# IO_Power_Decoupling.net
KiCad netlist of a schematic drawn in Altium Designer
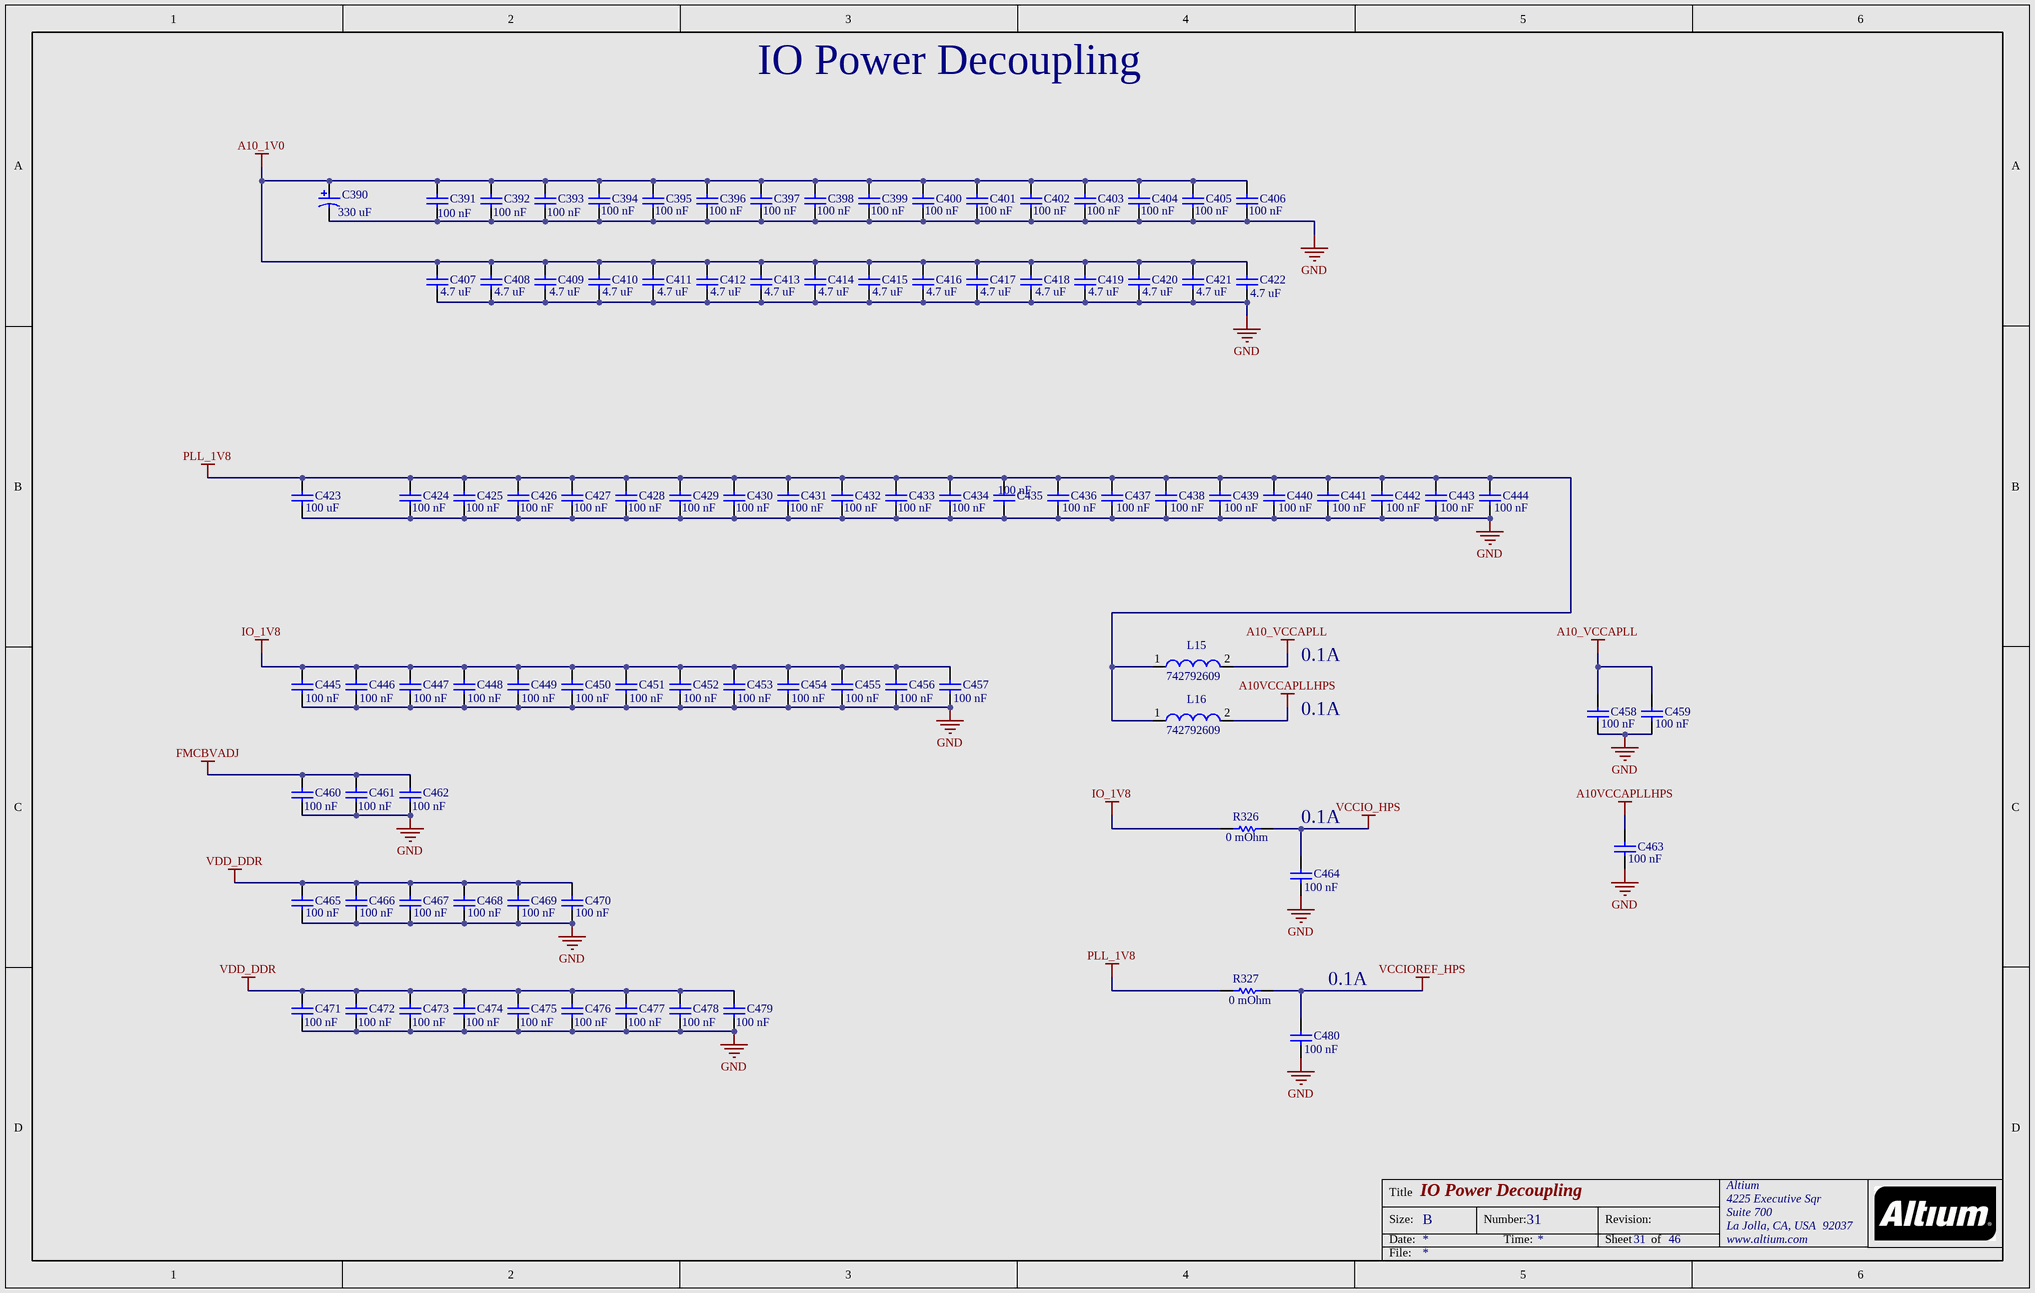
[diagram p0: IO_Power_Decoupling.SchDoc]

(export (version "E")
  (design (tool "Eeschema 10.0.6"))
  (components
    (comp (ref "C390")
      (value "T520B337M2R5ATE045")
      (footprint "KEMT-520-B-2_M")
      (description "Tantalum Capacitor, 330 uF, +/- 20%, 2.5 V, -55 to 105 degC, 2-Pin Molded, RoHS, Tape and Reel")
      (fields (field (name "CAPACITANCE") "330 uF"))
      (libsource (lib "Altium Content Vault") (part "CMP-1664-00002-2"))
    )
    (comp (ref "C391")
      (value "GRM033R60J104KE19D")
      (footprint "CAPC0603X33X15LL03T05")
      (description "Chip Capacitor, 100 nF, +/- 10%, 6.3 V, -55 to 85 degC, 0201 (0603 Metric), RoHS, Tape and Reel")
      (fields
        (field (name "TOLERANCE") "10%")
        (field (name "CAPACITANCE") "100 nF")
        (field (name "MANUFACTURER") "Basic Passives")
      )
      (libsource (lib "Altium Content Vault") (part "CAP-NP-2"))
    )
    (comp (ref "C392")
      (value "GRM033R60J104KE19D")
      (footprint "CAPC0603X33X15LL03T05")
      (description "Chip Capacitor, 100 nF, +/- 10%, 6.3 V, -55 to 85 degC, 0201 (0603 Metric), RoHS, Tape and Reel")
      (fields
        (field (name "TOLERANCE") "10%")
        (field (name "CAPACITANCE") "100 nF")
        (field (name "MANUFACTURER") "Basic Passives")
      )
      (libsource (lib "Altium Content Vault") (part "CAP-NP-2"))
    )
    (comp (ref "C393")
      (value "GRM033R60J104KE19D")
      (footprint "CAPC0603X33X15LL03T05")
      (description "Chip Capacitor, 100 nF, +/- 10%, 6.3 V, -55 to 85 degC, 0201 (0603 Metric), RoHS, Tape and Reel")
      (fields
        (field (name "TOLERANCE") "10%")
        (field (name "CAPACITANCE") "100 nF")
        (field (name "MANUFACTURER") "Basic Passives")
      )
      (libsource (lib "Altium Content Vault") (part "CAP-NP-2"))
    )
    (comp (ref "C394")
      (value "GRM033R60J104KE19D")
      (footprint "CAPC0603X33X15LL03T05")
      (description "Chip Capacitor, 100 nF, +/- 10%, 6.3 V, -55 to 85 degC, 0201 (0603 Metric), RoHS, Tape and Reel")
      (fields
        (field (name "TOLERANCE") "10%")
        (field (name "CAPACITANCE") "100 nF")
        (field (name "MANUFACTURER") "Basic Passives")
      )
      (libsource (lib "Altium Content Vault") (part "CAP-NP-2"))
    )
    (comp (ref "C395")
      (value "GRM033R60J104KE19D")
      (footprint "CAPC0603X33X15LL03T05")
      (description "Chip Capacitor, 100 nF, +/- 10%, 6.3 V, -55 to 85 degC, 0201 (0603 Metric), RoHS, Tape and Reel")
      (fields
        (field (name "TOLERANCE") "10%")
        (field (name "CAPACITANCE") "100 nF")
        (field (name "MANUFACTURER") "Basic Passives")
      )
      (libsource (lib "Altium Content Vault") (part "CAP-NP-2"))
    )
    (comp (ref "C396")
      (value "GRM033R60J104KE19D")
      (footprint "CAPC0603X33X15LL03T05")
      (description "Chip Capacitor, 100 nF, +/- 10%, 6.3 V, -55 to 85 degC, 0201 (0603 Metric), RoHS, Tape and Reel")
      (fields
        (field (name "TOLERANCE") "10%")
        (field (name "CAPACITANCE") "100 nF")
        (field (name "MANUFACTURER") "Basic Passives")
      )
      (libsource (lib "Altium Content Vault") (part "CAP-NP-2"))
    )
    (comp (ref "C397")
      (value "GRM033R60J104KE19D")
      (footprint "CAPC0603X33X15LL03T05")
      (description "Chip Capacitor, 100 nF, +/- 10%, 6.3 V, -55 to 85 degC, 0201 (0603 Metric), RoHS, Tape and Reel")
      (fields
        (field (name "TOLERANCE") "10%")
        (field (name "CAPACITANCE") "100 nF")
        (field (name "MANUFACTURER") "Basic Passives")
      )
      (libsource (lib "Altium Content Vault") (part "CAP-NP-2"))
    )
    (comp (ref "C398")
      (value "GRM033R60J104KE19D")
      (footprint "CAPC0603X33X15LL03T05")
      (description "Chip Capacitor, 100 nF, +/- 10%, 6.3 V, -55 to 85 degC, 0201 (0603 Metric), RoHS, Tape and Reel")
      (fields
        (field (name "TOLERANCE") "10%")
        (field (name "CAPACITANCE") "100 nF")
        (field (name "MANUFACTURER") "Basic Passives")
      )
      (libsource (lib "Altium Content Vault") (part "CAP-NP-2"))
    )
    (comp (ref "C399")
      (value "GRM033R60J104KE19D")
      (footprint "CAPC0603X33X15LL03T05")
      (description "Chip Capacitor, 100 nF, +/- 10%, 6.3 V, -55 to 85 degC, 0201 (0603 Metric), RoHS, Tape and Reel")
      (fields
        (field (name "TOLERANCE") "10%")
        (field (name "CAPACITANCE") "100 nF")
        (field (name "MANUFACTURER") "Basic Passives")
      )
      (libsource (lib "Altium Content Vault") (part "CAP-NP-2"))
    )
    (comp (ref "C400")
      (value "GRM033R60J104KE19D")
      (footprint "CAPC0603X33X15LL03T05")
      (description "Chip Capacitor, 100 nF, +/- 10%, 6.3 V, -55 to 85 degC, 0201 (0603 Metric), RoHS, Tape and Reel")
      (fields
        (field (name "TOLERANCE") "10%")
        (field (name "CAPACITANCE") "100 nF")
        (field (name "MANUFACTURER") "Basic Passives")
      )
      (libsource (lib "Altium Content Vault") (part "CAP-NP-2"))
    )
    (comp (ref "C401")
      (value "GRM033R60J104KE19D")
      (footprint "CAPC0603X33X15LL03T05")
      (description "Chip Capacitor, 100 nF, +/- 10%, 6.3 V, -55 to 85 degC, 0201 (0603 Metric), RoHS, Tape and Reel")
      (fields
        (field (name "TOLERANCE") "10%")
        (field (name "CAPACITANCE") "100 nF")
        (field (name "MANUFACTURER") "Basic Passives")
      )
      (libsource (lib "Altium Content Vault") (part "CAP-NP-2"))
    )
    (comp (ref "C402")
      (value "GRM033R60J104KE19D")
      (footprint "CAPC0603X33X15LL03T05")
      (description "Chip Capacitor, 100 nF, +/- 10%, 6.3 V, -55 to 85 degC, 0201 (0603 Metric), RoHS, Tape and Reel")
      (fields
        (field (name "TOLERANCE") "10%")
        (field (name "CAPACITANCE") "100 nF")
        (field (name "MANUFACTURER") "Basic Passives")
      )
      (libsource (lib "Altium Content Vault") (part "CAP-NP-2"))
    )
    (comp (ref "C403")
      (value "GRM033R60J104KE19D")
      (footprint "CAPC0603X33X15LL03T05")
      (description "Chip Capacitor, 100 nF, +/- 10%, 6.3 V, -55 to 85 degC, 0201 (0603 Metric), RoHS, Tape and Reel")
      (fields
        (field (name "TOLERANCE") "10%")
        (field (name "CAPACITANCE") "100 nF")
        (field (name "MANUFACTURER") "Basic Passives")
      )
      (libsource (lib "Altium Content Vault") (part "CAP-NP-2"))
    )
    (comp (ref "C404")
      (value "GRM033R60J104KE19D")
      (footprint "CAPC0603X33X15LL03T05")
      (description "Chip Capacitor, 100 nF, +/- 10%, 6.3 V, -55 to 85 degC, 0201 (0603 Metric), RoHS, Tape and Reel")
      (fields
        (field (name "TOLERANCE") "10%")
        (field (name "CAPACITANCE") "100 nF")
        (field (name "MANUFACTURER") "Basic Passives")
      )
      (libsource (lib "Altium Content Vault") (part "CAP-NP-2"))
    )
    (comp (ref "C405")
      (value "GRM033R60J104KE19D")
      (footprint "CAPC0603X33X15LL03T05")
      (description "Chip Capacitor, 100 nF, +/- 10%, 6.3 V, -55 to 85 degC, 0201 (0603 Metric), RoHS, Tape and Reel")
      (fields
        (field (name "TOLERANCE") "10%")
        (field (name "CAPACITANCE") "100 nF")
        (field (name "MANUFACTURER") "Basic Passives")
      )
      (libsource (lib "Altium Content Vault") (part "CAP-NP-2"))
    )
    (comp (ref "C406")
      (value "GRM033R60J104KE19D")
      (footprint "CAPC0603X33X15LL03T05")
      (description "Chip Capacitor, 100 nF, +/- 10%, 6.3 V, -55 to 85 degC, 0201 (0603 Metric), RoHS, Tape and Reel")
      (fields
        (field (name "TOLERANCE") "10%")
        (field (name "CAPACITANCE") "100 nF")
        (field (name "MANUFACTURER") "Basic Passives")
      )
      (libsource (lib "Altium Content Vault") (part "CAP-NP-2"))
    )
    (comp (ref "C407")
      (value "GRM155R60J475ME87D")
      (footprint "CAPC1005X55X25LL05T10")
      (description "Chip Capacitor, 4.7 uF, +/- 20%, 6.3 V, -55 to 85 degC, 0402 (1005 Metric), RoHS, Tape and Reel")
      (fields
        (field (name "TOLERANCE") "20%")
        (field (name "CAPACITANCE") "4.7 uF")
        (field (name "MANUFACTURER") "Basic Passives")
      )
      (libsource (lib "Altium Content Vault") (part "CAP-NP-2"))
    )
    (comp (ref "C408")
      (value "GRM155R60J475ME87D")
      (footprint "CAPC1005X55X25LL05T10")
      (description "Chip Capacitor, 4.7 uF, +/- 20%, 6.3 V, -55 to 85 degC, 0402 (1005 Metric), RoHS, Tape and Reel")
      (fields
        (field (name "TOLERANCE") "20%")
        (field (name "CAPACITANCE") "4.7 uF")
        (field (name "MANUFACTURER") "Basic Passives")
      )
      (libsource (lib "Altium Content Vault") (part "CAP-NP-2"))
    )
    (comp (ref "C409")
      (value "GRM155R60J475ME87D")
      (footprint "CAPC1005X55X25LL05T10")
      (description "Chip Capacitor, 4.7 uF, +/- 20%, 6.3 V, -55 to 85 degC, 0402 (1005 Metric), RoHS, Tape and Reel")
      (fields
        (field (name "TOLERANCE") "20%")
        (field (name "CAPACITANCE") "4.7 uF")
        (field (name "MANUFACTURER") "Basic Passives")
      )
      (libsource (lib "Altium Content Vault") (part "CAP-NP-2"))
    )
    (comp (ref "C410")
      (value "GRM155R60J475ME87D")
      (footprint "CAPC1005X55X25LL05T10")
      (description "Chip Capacitor, 4.7 uF, +/- 20%, 6.3 V, -55 to 85 degC, 0402 (1005 Metric), RoHS, Tape and Reel")
      (fields
        (field (name "TOLERANCE") "20%")
        (field (name "CAPACITANCE") "4.7 uF")
        (field (name "MANUFACTURER") "Basic Passives")
      )
      (libsource (lib "Altium Content Vault") (part "CAP-NP-2"))
    )
    (comp (ref "C411")
      (value "GRM155R60J475ME87D")
      (footprint "CAPC1005X55X25LL05T10")
      (description "Chip Capacitor, 4.7 uF, +/- 20%, 6.3 V, -55 to 85 degC, 0402 (1005 Metric), RoHS, Tape and Reel")
      (fields
        (field (name "TOLERANCE") "20%")
        (field (name "CAPACITANCE") "4.7 uF")
        (field (name "MANUFACTURER") "Basic Passives")
      )
      (libsource (lib "Altium Content Vault") (part "CAP-NP-2"))
    )
    (comp (ref "C412")
      (value "GRM155R60J475ME87D")
      (footprint "CAPC1005X55X25LL05T10")
      (description "Chip Capacitor, 4.7 uF, +/- 20%, 6.3 V, -55 to 85 degC, 0402 (1005 Metric), RoHS, Tape and Reel")
      (fields
        (field (name "TOLERANCE") "20%")
        (field (name "CAPACITANCE") "4.7 uF")
        (field (name "MANUFACTURER") "Basic Passives")
      )
      (libsource (lib "Altium Content Vault") (part "CAP-NP-2"))
    )
    (comp (ref "C413")
      (value "GRM155R60J475ME87D")
      (footprint "CAPC1005X55X25LL05T10")
      (description "Chip Capacitor, 4.7 uF, +/- 20%, 6.3 V, -55 to 85 degC, 0402 (1005 Metric), RoHS, Tape and Reel")
      (fields
        (field (name "TOLERANCE") "20%")
        (field (name "CAPACITANCE") "4.7 uF")
        (field (name "MANUFACTURER") "Basic Passives")
      )
      (libsource (lib "Altium Content Vault") (part "CAP-NP-2"))
    )
    (comp (ref "C414")
      (value "GRM155R60J475ME87D")
      (footprint "CAPC1005X55X25LL05T10")
      (description "Chip Capacitor, 4.7 uF, +/- 20%, 6.3 V, -55 to 85 degC, 0402 (1005 Metric), RoHS, Tape and Reel")
      (fields
        (field (name "TOLERANCE") "20%")
        (field (name "CAPACITANCE") "4.7 uF")
        (field (name "MANUFACTURER") "Basic Passives")
      )
      (libsource (lib "Altium Content Vault") (part "CAP-NP-2"))
    )
    (comp (ref "C415")
      (value "GRM155R60J475ME87D")
      (footprint "CAPC1005X55X25LL05T10")
      (description "Chip Capacitor, 4.7 uF, +/- 20%, 6.3 V, -55 to 85 degC, 0402 (1005 Metric), RoHS, Tape and Reel")
      (fields
        (field (name "TOLERANCE") "20%")
        (field (name "CAPACITANCE") "4.7 uF")
        (field (name "MANUFACTURER") "Basic Passives")
      )
      (libsource (lib "Altium Content Vault") (part "CAP-NP-2"))
    )
    (comp (ref "C416")
      (value "GRM155R60J475ME87D")
      (footprint "CAPC1005X55X25LL05T10")
      (description "Chip Capacitor, 4.7 uF, +/- 20%, 6.3 V, -55 to 85 degC, 0402 (1005 Metric), RoHS, Tape and Reel")
      (fields
        (field (name "TOLERANCE") "20%")
        (field (name "CAPACITANCE") "4.7 uF")
        (field (name "MANUFACTURER") "Basic Passives")
      )
      (libsource (lib "Altium Content Vault") (part "CAP-NP-2"))
    )
    (comp (ref "C417")
      (value "GRM155R60J475ME87D")
      (footprint "CAPC1005X55X25LL05T10")
      (description "Chip Capacitor, 4.7 uF, +/- 20%, 6.3 V, -55 to 85 degC, 0402 (1005 Metric), RoHS, Tape and Reel")
      (fields
        (field (name "TOLERANCE") "20%")
        (field (name "CAPACITANCE") "4.7 uF")
        (field (name "MANUFACTURER") "Basic Passives")
      )
      (libsource (lib "Altium Content Vault") (part "CAP-NP-2"))
    )
    (comp (ref "C418")
      (value "GRM155R60J475ME87D")
      (footprint "CAPC1005X55X25LL05T10")
      (description "Chip Capacitor, 4.7 uF, +/- 20%, 6.3 V, -55 to 85 degC, 0402 (1005 Metric), RoHS, Tape and Reel")
      (fields
        (field (name "TOLERANCE") "20%")
        (field (name "CAPACITANCE") "4.7 uF")
        (field (name "MANUFACTURER") "Basic Passives")
      )
      (libsource (lib "Altium Content Vault") (part "CAP-NP-2"))
    )
    (comp (ref "C419")
      (value "GRM155R60J475ME87D")
      (footprint "CAPC1005X55X25LL05T10")
      (description "Chip Capacitor, 4.7 uF, +/- 20%, 6.3 V, -55 to 85 degC, 0402 (1005 Metric), RoHS, Tape and Reel")
      (fields
        (field (name "TOLERANCE") "20%")
        (field (name "CAPACITANCE") "4.7 uF")
        (field (name "MANUFACTURER") "Basic Passives")
      )
      (libsource (lib "Altium Content Vault") (part "CAP-NP-2"))
    )
    (comp (ref "C420")
      (value "GRM155R60J475ME87D")
      (footprint "CAPC1005X55X25LL05T10")
      (description "Chip Capacitor, 4.7 uF, +/- 20%, 6.3 V, -55 to 85 degC, 0402 (1005 Metric), RoHS, Tape and Reel")
      (fields
        (field (name "TOLERANCE") "20%")
        (field (name "CAPACITANCE") "4.7 uF")
        (field (name "MANUFACTURER") "Basic Passives")
      )
      (libsource (lib "Altium Content Vault") (part "CAP-NP-2"))
    )
    (comp (ref "C421")
      (value "GRM155R60J475ME87D")
      (footprint "CAPC1005X55X25LL05T10")
      (description "Chip Capacitor, 4.7 uF, +/- 20%, 6.3 V, -55 to 85 degC, 0402 (1005 Metric), RoHS, Tape and Reel")
      (fields
        (field (name "TOLERANCE") "20%")
        (field (name "CAPACITANCE") "4.7 uF")
        (field (name "MANUFACTURER") "Basic Passives")
      )
      (libsource (lib "Altium Content Vault") (part "CAP-NP-2"))
    )
    (comp (ref "C422")
      (value "GRM155R60J475ME87D")
      (footprint "CAPC1005X55X25LL05T10")
      (description "Chip Capacitor, 4.7 uF, +/- 20%, 6.3 V, -55 to 85 degC, 0402 (1005 Metric), RoHS, Tape and Reel")
      (fields
        (field (name "TOLERANCE") "20%")
        (field (name "CAPACITANCE") "4.7 uF")
        (field (name "MANUFACTURER") "Basic Passives")
      )
      (libsource (lib "Altium Content Vault") (part "CAP-NP-2"))
    )
    (comp (ref "C423")
      (value "GRM31CR60J107ME39L")
      (footprint "CAPC3216X190X55ML30T25")
      (description "Chip Capacitor, 100 uF, +/- 20%, 6.3 V, -55 to 85 degC, 1206 (3216 Metric), RoHS, Tape and Reel")
      (fields (field (name "TOLERANCE") "20%") (field (name "CAPACITANCE") "100 uF"))
      (libsource (lib "Altium Content Vault") (part "CAP-NP-2"))
    )
    (comp (ref "C424")
      (value "GRM033R60J104KE19D")
      (footprint "CAPC0603X33X15LL03T05")
      (description "Chip Capacitor, 100 nF, +/- 10%, 6.3 V, -55 to 85 degC, 0201 (0603 Metric), RoHS, Tape and Reel")
      (fields
        (field (name "TOLERANCE") "10%")
        (field (name "CAPACITANCE") "100 nF")
        (field (name "MANUFACTURER") "Basic Passives")
      )
      (libsource (lib "Altium Content Vault") (part "CAP-NP-2"))
    )
    (comp (ref "C425")
      (value "GRM033R60J104KE19D")
      (footprint "CAPC0603X33X15LL03T05")
      (description "Chip Capacitor, 100 nF, +/- 10%, 6.3 V, -55 to 85 degC, 0201 (0603 Metric), RoHS, Tape and Reel")
      (fields
        (field (name "TOLERANCE") "10%")
        (field (name "CAPACITANCE") "100 nF")
        (field (name "MANUFACTURER") "Basic Passives")
      )
      (libsource (lib "Altium Content Vault") (part "CAP-NP-2"))
    )
    (comp (ref "C426")
      (value "GRM033R60J104KE19D")
      (footprint "CAPC0603X33X15LL03T05")
      (description "Chip Capacitor, 100 nF, +/- 10%, 6.3 V, -55 to 85 degC, 0201 (0603 Metric), RoHS, Tape and Reel")
      (fields
        (field (name "TOLERANCE") "10%")
        (field (name "CAPACITANCE") "100 nF")
        (field (name "MANUFACTURER") "Basic Passives")
      )
      (libsource (lib "Altium Content Vault") (part "CAP-NP-2"))
    )
    (comp (ref "C427")
      (value "GRM033R60J104KE19D")
      (footprint "CAPC0603X33X15LL03T05")
      (description "Chip Capacitor, 100 nF, +/- 10%, 6.3 V, -55 to 85 degC, 0201 (0603 Metric), RoHS, Tape and Reel")
      (fields
        (field (name "TOLERANCE") "10%")
        (field (name "CAPACITANCE") "100 nF")
        (field (name "MANUFACTURER") "Basic Passives")
      )
      (libsource (lib "Altium Content Vault") (part "CAP-NP-2"))
    )
    (comp (ref "C428")
      (value "GRM033R60J104KE19D")
      (footprint "CAPC0603X33X15LL03T05")
      (description "Chip Capacitor, 100 nF, +/- 10%, 6.3 V, -55 to 85 degC, 0201 (0603 Metric), RoHS, Tape and Reel")
      (fields
        (field (name "TOLERANCE") "10%")
        (field (name "CAPACITANCE") "100 nF")
        (field (name "MANUFACTURER") "Basic Passives")
      )
      (libsource (lib "Altium Content Vault") (part "CAP-NP-2"))
    )
    (comp (ref "C429")
      (value "GRM033R60J104KE19D")
      (footprint "CAPC0603X33X15LL03T05")
      (description "Chip Capacitor, 100 nF, +/- 10%, 6.3 V, -55 to 85 degC, 0201 (0603 Metric), RoHS, Tape and Reel")
      (fields
        (field (name "TOLERANCE") "10%")
        (field (name "CAPACITANCE") "100 nF")
        (field (name "MANUFACTURER") "Basic Passives")
      )
      (libsource (lib "Altium Content Vault") (part "CAP-NP-2"))
    )
    (comp (ref "C430")
      (value "GRM033R60J104KE19D")
      (footprint "CAPC0603X33X15LL03T05")
      (description "Chip Capacitor, 100 nF, +/- 10%, 6.3 V, -55 to 85 degC, 0201 (0603 Metric), RoHS, Tape and Reel")
      (fields
        (field (name "TOLERANCE") "10%")
        (field (name "CAPACITANCE") "100 nF")
        (field (name "MANUFACTURER") "Basic Passives")
      )
      (libsource (lib "Altium Content Vault") (part "CAP-NP-2"))
    )
    (comp (ref "C431")
      (value "GRM033R60J104KE19D")
      (footprint "CAPC0603X33X15LL03T05")
      (description "Chip Capacitor, 100 nF, +/- 10%, 6.3 V, -55 to 85 degC, 0201 (0603 Metric), RoHS, Tape and Reel")
      (fields
        (field (name "TOLERANCE") "10%")
        (field (name "CAPACITANCE") "100 nF")
        (field (name "MANUFACTURER") "Basic Passives")
      )
      (libsource (lib "Altium Content Vault") (part "CAP-NP-2"))
    )
    (comp (ref "C432")
      (value "GRM033R60J104KE19D")
      (footprint "CAPC0603X33X15LL03T05")
      (description "Chip Capacitor, 100 nF, +/- 10%, 6.3 V, -55 to 85 degC, 0201 (0603 Metric), RoHS, Tape and Reel")
      (fields
        (field (name "TOLERANCE") "10%")
        (field (name "CAPACITANCE") "100 nF")
        (field (name "MANUFACTURER") "Basic Passives")
      )
      (libsource (lib "Altium Content Vault") (part "CAP-NP-2"))
    )
    (comp (ref "C433")
      (value "GRM033R60J104KE19D")
      (footprint "CAPC0603X33X15LL03T05")
      (description "Chip Capacitor, 100 nF, +/- 10%, 6.3 V, -55 to 85 degC, 0201 (0603 Metric), RoHS, Tape and Reel")
      (fields
        (field (name "TOLERANCE") "10%")
        (field (name "CAPACITANCE") "100 nF")
        (field (name "MANUFACTURER") "Basic Passives")
      )
      (libsource (lib "Altium Content Vault") (part "CAP-NP-2"))
    )
    (comp (ref "C434")
      (value "GRM033R60J104KE19D")
      (footprint "CAPC0603X33X15LL03T05")
      (description "Chip Capacitor, 100 nF, +/- 10%, 6.3 V, -55 to 85 degC, 0201 (0603 Metric), RoHS, Tape and Reel")
      (fields
        (field (name "TOLERANCE") "10%")
        (field (name "CAPACITANCE") "100 nF")
        (field (name "MANUFACTURER") "Basic Passives")
      )
      (libsource (lib "Altium Content Vault") (part "CAP-NP-2"))
    )
    (comp (ref "C435")
      (value "GRM033R60J104KE19D")
      (footprint "CAPC0603X33X15LL03T05")
      (description "Chip Capacitor, 100 nF, +/- 10%, 6.3 V, -55 to 85 degC, 0201 (0603 Metric), RoHS, Tape and Reel")
      (fields
        (field (name "TOLERANCE") "10%")
        (field (name "CAPACITANCE") "100 nF")
        (field (name "MANUFACTURER") "Basic Passives")
      )
      (libsource (lib "Altium Content Vault") (part "CAP-NP-2"))
    )
    (comp (ref "C436")
      (value "GRM033R60J104KE19D")
      (footprint "CAPC0603X33X15LL03T05")
      (description "Chip Capacitor, 100 nF, +/- 10%, 6.3 V, -55 to 85 degC, 0201 (0603 Metric), RoHS, Tape and Reel")
      (fields
        (field (name "TOLERANCE") "10%")
        (field (name "CAPACITANCE") "100 nF")
        (field (name "MANUFACTURER") "Basic Passives")
      )
      (libsource (lib "Altium Content Vault") (part "CAP-NP-2"))
    )
    (comp (ref "C437")
      (value "GRM033R60J104KE19D")
      (footprint "CAPC0603X33X15LL03T05")
      (description "Chip Capacitor, 100 nF, +/- 10%, 6.3 V, -55 to 85 degC, 0201 (0603 Metric), RoHS, Tape and Reel")
      (fields
        (field (name "TOLERANCE") "10%")
        (field (name "CAPACITANCE") "100 nF")
        (field (name "MANUFACTURER") "Basic Passives")
      )
      (libsource (lib "Altium Content Vault") (part "CAP-NP-2"))
    )
    (comp (ref "C438")
      (value "GRM033R60J104KE19D")
      (footprint "CAPC0603X33X15LL03T05")
      (description "Chip Capacitor, 100 nF, +/- 10%, 6.3 V, -55 to 85 degC, 0201 (0603 Metric), RoHS, Tape and Reel")
      (fields
        (field (name "TOLERANCE") "10%")
        (field (name "CAPACITANCE") "100 nF")
        (field (name "MANUFACTURER") "Basic Passives")
      )
      (libsource (lib "Altium Content Vault") (part "CAP-NP-2"))
    )
    (comp (ref "C439")
      (value "GRM033R60J104KE19D")
      (footprint "CAPC0603X33X15LL03T05")
      (description "Chip Capacitor, 100 nF, +/- 10%, 6.3 V, -55 to 85 degC, 0201 (0603 Metric), RoHS, Tape and Reel")
      (fields
        (field (name "TOLERANCE") "10%")
        (field (name "CAPACITANCE") "100 nF")
        (field (name "MANUFACTURER") "Basic Passives")
      )
      (libsource (lib "Altium Content Vault") (part "CAP-NP-2"))
    )
    (comp (ref "C440")
      (value "GRM033R60J104KE19D")
      (footprint "CAPC0603X33X15LL03T05")
      (description "Chip Capacitor, 100 nF, +/- 10%, 6.3 V, -55 to 85 degC, 0201 (0603 Metric), RoHS, Tape and Reel")
      (fields
        (field (name "TOLERANCE") "10%")
        (field (name "CAPACITANCE") "100 nF")
        (field (name "MANUFACTURER") "Basic Passives")
      )
      (libsource (lib "Altium Content Vault") (part "CAP-NP-2"))
    )
    (comp (ref "C441")
      (value "GRM033R60J104KE19D")
      (footprint "CAPC0603X33X15LL03T05")
      (description "Chip Capacitor, 100 nF, +/- 10%, 6.3 V, -55 to 85 degC, 0201 (0603 Metric), RoHS, Tape and Reel")
      (fields
        (field (name "TOLERANCE") "10%")
        (field (name "CAPACITANCE") "100 nF")
        (field (name "MANUFACTURER") "Basic Passives")
      )
      (libsource (lib "Altium Content Vault") (part "CAP-NP-2"))
    )
    (comp (ref "C442")
      (value "GRM033R60J104KE19D")
      (footprint "CAPC0603X33X15LL03T05")
      (description "Chip Capacitor, 100 nF, +/- 10%, 6.3 V, -55 to 85 degC, 0201 (0603 Metric), RoHS, Tape and Reel")
      (fields
        (field (name "TOLERANCE") "10%")
        (field (name "CAPACITANCE") "100 nF")
        (field (name "MANUFACTURER") "Basic Passives")
      )
      (libsource (lib "Altium Content Vault") (part "CAP-NP-2"))
    )
    (comp (ref "C443")
      (value "GRM033R60J104KE19D")
      (footprint "CAPC0603X33X15LL03T05")
      (description "Chip Capacitor, 100 nF, +/- 10%, 6.3 V, -55 to 85 degC, 0201 (0603 Metric), RoHS, Tape and Reel")
      (fields
        (field (name "TOLERANCE") "10%")
        (field (name "CAPACITANCE") "100 nF")
        (field (name "MANUFACTURER") "Basic Passives")
      )
      (libsource (lib "Altium Content Vault") (part "CAP-NP-2"))
    )
    (comp (ref "C444")
      (value "GRM033R60J104KE19D")
      (footprint "CAPC0603X33X15LL03T05")
      (description "Chip Capacitor, 100 nF, +/- 10%, 6.3 V, -55 to 85 degC, 0201 (0603 Metric), RoHS, Tape and Reel")
      (fields
        (field (name "TOLERANCE") "10%")
        (field (name "CAPACITANCE") "100 nF")
        (field (name "MANUFACTURER") "Basic Passives")
      )
      (libsource (lib "Altium Content Vault") (part "CAP-NP-2"))
    )
    (comp (ref "C445")
      (value "GRM033R60J104KE19D")
      (footprint "CAPC0603X33X15LL03T05")
      (description "Chip Capacitor, 100 nF, +/- 10%, 6.3 V, -55 to 85 degC, 0201 (0603 Metric), RoHS, Tape and Reel")
      (fields
        (field (name "TOLERANCE") "10%")
        (field (name "CAPACITANCE") "100 nF")
        (field (name "MANUFACTURER") "Basic Passives")
      )
      (libsource (lib "Altium Content Vault") (part "CAP-NP-2"))
    )
    (comp (ref "C446")
      (value "GRM033R60J104KE19D")
      (footprint "CAPC0603X33X15LL03T05")
      (description "Chip Capacitor, 100 nF, +/- 10%, 6.3 V, -55 to 85 degC, 0201 (0603 Metric), RoHS, Tape and Reel")
      (fields
        (field (name "TOLERANCE") "10%")
        (field (name "CAPACITANCE") "100 nF")
        (field (name "MANUFACTURER") "Basic Passives")
      )
      (libsource (lib "Altium Content Vault") (part "CAP-NP-2"))
    )
    (comp (ref "C447")
      (value "GRM033R60J104KE19D")
      (footprint "CAPC0603X33X15LL03T05")
      (description "Chip Capacitor, 100 nF, +/- 10%, 6.3 V, -55 to 85 degC, 0201 (0603 Metric), RoHS, Tape and Reel")
      (fields
        (field (name "TOLERANCE") "10%")
        (field (name "CAPACITANCE") "100 nF")
        (field (name "MANUFACTURER") "Basic Passives")
      )
      (libsource (lib "Altium Content Vault") (part "CAP-NP-2"))
    )
    (comp (ref "C448")
      (value "GRM033R60J104KE19D")
      (footprint "CAPC0603X33X15LL03T05")
      (description "Chip Capacitor, 100 nF, +/- 10%, 6.3 V, -55 to 85 degC, 0201 (0603 Metric), RoHS, Tape and Reel")
      (fields
        (field (name "TOLERANCE") "10%")
        (field (name "CAPACITANCE") "100 nF")
        (field (name "MANUFACTURER") "Basic Passives")
      )
      (libsource (lib "Altium Content Vault") (part "CAP-NP-2"))
    )
    (comp (ref "C449")
      (value "GRM033R60J104KE19D")
      (footprint "CAPC0603X33X15LL03T05")
      (description "Chip Capacitor, 100 nF, +/- 10%, 6.3 V, -55 to 85 degC, 0201 (0603 Metric), RoHS, Tape and Reel")
      (fields
        (field (name "TOLERANCE") "10%")
        (field (name "CAPACITANCE") "100 nF")
        (field (name "MANUFACTURER") "Basic Passives")
      )
      (libsource (lib "Altium Content Vault") (part "CAP-NP-2"))
    )
    (comp (ref "C450")
      (value "GRM033R60J104KE19D")
      (footprint "CAPC0603X33X15LL03T05")
      (description "Chip Capacitor, 100 nF, +/- 10%, 6.3 V, -55 to 85 degC, 0201 (0603 Metric), RoHS, Tape and Reel")
      (fields
        (field (name "TOLERANCE") "10%")
        (field (name "CAPACITANCE") "100 nF")
        (field (name "MANUFACTURER") "Basic Passives")
      )
      (libsource (lib "Altium Content Vault") (part "CAP-NP-2"))
    )
    (comp (ref "C451")
      (value "GRM033R60J104KE19D")
      (footprint "CAPC0603X33X15LL03T05")
      (description "Chip Capacitor, 100 nF, +/- 10%, 6.3 V, -55 to 85 degC, 0201 (0603 Metric), RoHS, Tape and Reel")
      (fields
        (field (name "TOLERANCE") "10%")
        (field (name "CAPACITANCE") "100 nF")
        (field (name "MANUFACTURER") "Basic Passives")
      )
      (libsource (lib "Altium Content Vault") (part "CAP-NP-2"))
    )
    (comp (ref "C452")
      (value "GRM033R60J104KE19D")
      (footprint "CAPC0603X33X15LL03T05")
      (description "Chip Capacitor, 100 nF, +/- 10%, 6.3 V, -55 to 85 degC, 0201 (0603 Metric), RoHS, Tape and Reel")
      (fields
        (field (name "TOLERANCE") "10%")
        (field (name "CAPACITANCE") "100 nF")
        (field (name "MANUFACTURER") "Basic Passives")
      )
      (libsource (lib "Altium Content Vault") (part "CAP-NP-2"))
    )
    (comp (ref "C453")
      (value "GRM033R60J104KE19D")
      (footprint "CAPC0603X33X15LL03T05")
      (description "Chip Capacitor, 100 nF, +/- 10%, 6.3 V, -55 to 85 degC, 0201 (0603 Metric), RoHS, Tape and Reel")
      (fields
        (field (name "TOLERANCE") "10%")
        (field (name "CAPACITANCE") "100 nF")
        (field (name "MANUFACTURER") "Basic Passives")
      )
      (libsource (lib "Altium Content Vault") (part "CAP-NP-2"))
    )
    (comp (ref "C454")
      (value "GRM033R60J104KE19D")
      (footprint "CAPC0603X33X15LL03T05")
      (description "Chip Capacitor, 100 nF, +/- 10%, 6.3 V, -55 to 85 degC, 0201 (0603 Metric), RoHS, Tape and Reel")
      (fields
        (field (name "TOLERANCE") "10%")
        (field (name "CAPACITANCE") "100 nF")
        (field (name "MANUFACTURER") "Basic Passives")
      )
      (libsource (lib "Altium Content Vault") (part "CAP-NP-2"))
    )
    (comp (ref "C455")
      (value "GRM033R60J104KE19D")
      (footprint "CAPC0603X33X15LL03T05")
      (description "Chip Capacitor, 100 nF, +/- 10%, 6.3 V, -55 to 85 degC, 0201 (0603 Metric), RoHS, Tape and Reel")
      (fields
        (field (name "TOLERANCE") "10%")
        (field (name "CAPACITANCE") "100 nF")
        (field (name "MANUFACTURER") "Basic Passives")
      )
      (libsource (lib "Altium Content Vault") (part "CAP-NP-2"))
    )
    (comp (ref "C456")
      (value "GRM033R60J104KE19D")
      (footprint "CAPC0603X33X15LL03T05")
      (description "Chip Capacitor, 100 nF, +/- 10%, 6.3 V, -55 to 85 degC, 0201 (0603 Metric), RoHS, Tape and Reel")
      (fields
        (field (name "TOLERANCE") "10%")
        (field (name "CAPACITANCE") "100 nF")
        (field (name "MANUFACTURER") "Basic Passives")
      )
      (libsource (lib "Altium Content Vault") (part "CAP-NP-2"))
    )
    (comp (ref "C457")
      (value "GRM033R60J104KE19D")
      (footprint "CAPC0603X33X15LL03T05")
      (description "Chip Capacitor, 100 nF, +/- 10%, 6.3 V, -55 to 85 degC, 0201 (0603 Metric), RoHS, Tape and Reel")
      (fields
        (field (name "TOLERANCE") "10%")
        (field (name "CAPACITANCE") "100 nF")
        (field (name "MANUFACTURER") "Basic Passives")
      )
      (libsource (lib "Altium Content Vault") (part "CAP-NP-2"))
    )
    (comp (ref "C458")
      (value "GRM033R60J104KE19D")
      (footprint "CAPC0603X33X15LL03T05")
      (description "Chip Capacitor, 100 nF, +/- 10%, 6.3 V, -55 to 85 degC, 0201 (0603 Metric), RoHS, Tape and Reel")
      (fields
        (field (name "TOLERANCE") "10%")
        (field (name "CAPACITANCE") "100 nF")
        (field (name "MANUFACTURER") "Basic Passives")
      )
      (libsource (lib "Altium Content Vault") (part "CAP-NP-2"))
    )
    (comp (ref "C459")
      (value "GRM033R60J104KE19D")
      (footprint "CAPC0603X33X15LL03T05")
      (description "Chip Capacitor, 100 nF, +/- 10%, 6.3 V, -55 to 85 degC, 0201 (0603 Metric), RoHS, Tape and Reel")
      (fields
        (field (name "TOLERANCE") "10%")
        (field (name "CAPACITANCE") "100 nF")
        (field (name "MANUFACTURER") "Basic Passives")
      )
      (libsource (lib "Altium Content Vault") (part "CAP-NP-2"))
    )
    (comp (ref "C460")
      (value "GRM033R60J104KE19D")
      (footprint "CAPC0603X33X15LL03T05")
      (description "Chip Capacitor, 100 nF, +/- 10%, 6.3 V, -55 to 85 degC, 0201 (0603 Metric), RoHS, Tape and Reel")
      (fields
        (field (name "TOLERANCE") "10%")
        (field (name "CAPACITANCE") "100 nF")
        (field (name "MANUFACTURER") "Basic Passives")
      )
      (libsource (lib "Altium Content Vault") (part "CAP-NP-2"))
    )
    (comp (ref "C461")
      (value "GRM033R60J104KE19D")
      (footprint "CAPC0603X33X15LL03T05")
      (description "Chip Capacitor, 100 nF, +/- 10%, 6.3 V, -55 to 85 degC, 0201 (0603 Metric), RoHS, Tape and Reel")
      (fields
        (field (name "TOLERANCE") "10%")
        (field (name "CAPACITANCE") "100 nF")
        (field (name "MANUFACTURER") "Basic Passives")
      )
      (libsource (lib "Altium Content Vault") (part "CAP-NP-2"))
    )
    (comp (ref "C462")
      (value "GRM033R60J104KE19D")
      (footprint "CAPC0603X33X15LL03T05")
      (description "Chip Capacitor, 100 nF, +/- 10%, 6.3 V, -55 to 85 degC, 0201 (0603 Metric), RoHS, Tape and Reel")
      (fields
        (field (name "TOLERANCE") "10%")
        (field (name "CAPACITANCE") "100 nF")
        (field (name "MANUFACTURER") "Basic Passives")
      )
      (libsource (lib "Altium Content Vault") (part "CAP-NP-2"))
    )
    (comp (ref "C463")
      (value "GRM033R60J104KE19D")
      (footprint "CAPC0603X33X15LL03T05")
      (description "Chip Capacitor, 100 nF, +/- 10%, 6.3 V, -55 to 85 degC, 0201 (0603 Metric), RoHS, Tape and Reel")
      (fields
        (field (name "TOLERANCE") "10%")
        (field (name "CAPACITANCE") "100 nF")
        (field (name "MANUFACTURER") "Basic Passives")
      )
      (libsource (lib "Altium Content Vault") (part "CAP-NP-2"))
    )
    (comp (ref "C464")
      (value "GRM033R60J104KE19D")
      (footprint "CAPC0603X33X15LL03T05")
      (description "Chip Capacitor, 100 nF, +/- 10%, 6.3 V, -55 to 85 degC, 0201 (0603 Metric), RoHS, Tape and Reel")
      (fields
        (field (name "TOLERANCE") "10%")
        (field (name "CAPACITANCE") "100 nF")
        (field (name "MANUFACTURER") "Basic Passives")
      )
      (libsource (lib "Altium Content Vault") (part "CAP-NP-2"))
    )
    (comp (ref "C465")
      (value "GRM033R60J104KE19D")
      (footprint "CAPC0603X33X15LL03T05")
      (description "Chip Capacitor, 100 nF, +/- 10%, 6.3 V, -55 to 85 degC, 0201 (0603 Metric), RoHS, Tape and Reel")
      (fields
        (field (name "TOLERANCE") "10%")
        (field (name "CAPACITANCE") "100 nF")
        (field (name "MANUFACTURER") "Basic Passives")
      )
      (libsource (lib "Altium Content Vault") (part "CAP-NP-2"))
    )
    (comp (ref "C466")
      (value "GRM033R60J104KE19D")
      (footprint "CAPC0603X33X15LL03T05")
      (description "Chip Capacitor, 100 nF, +/- 10%, 6.3 V, -55 to 85 degC, 0201 (0603 Metric), RoHS, Tape and Reel")
      (fields
        (field (name "TOLERANCE") "10%")
        (field (name "CAPACITANCE") "100 nF")
        (field (name "MANUFACTURER") "Basic Passives")
      )
      (libsource (lib "Altium Content Vault") (part "CAP-NP-2"))
    )
    (comp (ref "C467")
      (value "GRM033R60J104KE19D")
      (footprint "CAPC0603X33X15LL03T05")
      (description "Chip Capacitor, 100 nF, +/- 10%, 6.3 V, -55 to 85 degC, 0201 (0603 Metric), RoHS, Tape and Reel")
      (fields
        (field (name "TOLERANCE") "10%")
        (field (name "CAPACITANCE") "100 nF")
        (field (name "MANUFACTURER") "Basic Passives")
      )
      (libsource (lib "Altium Content Vault") (part "CAP-NP-2"))
    )
    (comp (ref "C468")
      (value "GRM033R60J104KE19D")
      (footprint "CAPC0603X33X15LL03T05")
      (description "Chip Capacitor, 100 nF, +/- 10%, 6.3 V, -55 to 85 degC, 0201 (0603 Metric), RoHS, Tape and Reel")
      (fields
        (field (name "TOLERANCE") "10%")
        (field (name "CAPACITANCE") "100 nF")
        (field (name "MANUFACTURER") "Basic Passives")
      )
      (libsource (lib "Altium Content Vault") (part "CAP-NP-2"))
    )
    (comp (ref "C469")
      (value "GRM033R60J104KE19D")
      (footprint "CAPC0603X33X15LL03T05")
      (description "Chip Capacitor, 100 nF, +/- 10%, 6.3 V, -55 to 85 degC, 0201 (0603 Metric), RoHS, Tape and Reel")
      (fields
        (field (name "TOLERANCE") "10%")
        (field (name "CAPACITANCE") "100 nF")
        (field (name "MANUFACTURER") "Basic Passives")
      )
      (libsource (lib "Altium Content Vault") (part "CAP-NP-2"))
    )
    (comp (ref "C470")
      (value "GRM033R60J104KE19D")
      (footprint "CAPC0603X33X15LL03T05")
      (description "Chip Capacitor, 100 nF, +/- 10%, 6.3 V, -55 to 85 degC, 0201 (0603 Metric), RoHS, Tape and Reel")
      (fields
        (field (name "TOLERANCE") "10%")
        (field (name "CAPACITANCE") "100 nF")
        (field (name "MANUFACTURER") "Basic Passives")
      )
      (libsource (lib "Altium Content Vault") (part "CAP-NP-2"))
    )
    (comp (ref "C471")
      (value "GRM033R60J104KE19D")
      (footprint "CAPC0603X33X15LL03T05")
      (description "Chip Capacitor, 100 nF, +/- 10%, 6.3 V, -55 to 85 degC, 0201 (0603 Metric), RoHS, Tape and Reel")
      (fields
        (field (name "TOLERANCE") "10%")
        (field (name "CAPACITANCE") "100 nF")
        (field (name "MANUFACTURER") "Basic Passives")
      )
      (libsource (lib "Altium Content Vault") (part "CAP-NP-2"))
    )
    (comp (ref "C472")
      (value "GRM033R60J104KE19D")
      (footprint "CAPC0603X33X15LL03T05")
      (description "Chip Capacitor, 100 nF, +/- 10%, 6.3 V, -55 to 85 degC, 0201 (0603 Metric), RoHS, Tape and Reel")
      (fields
        (field (name "TOLERANCE") "10%")
        (field (name "CAPACITANCE") "100 nF")
        (field (name "MANUFACTURER") "Basic Passives")
      )
      (libsource (lib "Altium Content Vault") (part "CAP-NP-2"))
    )
    (comp (ref "C473")
      (value "GRM033R60J104KE19D")
      (footprint "CAPC0603X33X15LL03T05")
      (description "Chip Capacitor, 100 nF, +/- 10%, 6.3 V, -55 to 85 degC, 0201 (0603 Metric), RoHS, Tape and Reel")
      (fields
        (field (name "TOLERANCE") "10%")
        (field (name "CAPACITANCE") "100 nF")
        (field (name "MANUFACTURER") "Basic Passives")
      )
      (libsource (lib "Altium Content Vault") (part "CAP-NP-2"))
    )
    (comp (ref "C474")
      (value "GRM033R60J104KE19D")
      (footprint "CAPC0603X33X15LL03T05")
      (description "Chip Capacitor, 100 nF, +/- 10%, 6.3 V, -55 to 85 degC, 0201 (0603 Metric), RoHS, Tape and Reel")
      (fields
        (field (name "TOLERANCE") "10%")
        (field (name "CAPACITANCE") "100 nF")
        (field (name "MANUFACTURER") "Basic Passives")
      )
      (libsource (lib "Altium Content Vault") (part "CAP-NP-2"))
    )
    (comp (ref "C475")
      (value "GRM033R60J104KE19D")
      (footprint "CAPC0603X33X15LL03T05")
      (description "Chip Capacitor, 100 nF, +/- 10%, 6.3 V, -55 to 85 degC, 0201 (0603 Metric), RoHS, Tape and Reel")
      (fields
        (field (name "TOLERANCE") "10%")
        (field (name "CAPACITANCE") "100 nF")
        (field (name "MANUFACTURER") "Basic Passives")
      )
      (libsource (lib "Altium Content Vault") (part "CAP-NP-2"))
    )
    (comp (ref "C476")
      (value "GRM033R60J104KE19D")
      (footprint "CAPC0603X33X15LL03T05")
      (description "Chip Capacitor, 100 nF, +/- 10%, 6.3 V, -55 to 85 degC, 0201 (0603 Metric), RoHS, Tape and Reel")
      (fields
        (field (name "TOLERANCE") "10%")
        (field (name "CAPACITANCE") "100 nF")
        (field (name "MANUFACTURER") "Basic Passives")
      )
      (libsource (lib "Altium Content Vault") (part "CAP-NP-2"))
    )
    (comp (ref "C477")
      (value "GRM033R60J104KE19D")
      (footprint "CAPC0603X33X15LL03T05")
      (description "Chip Capacitor, 100 nF, +/- 10%, 6.3 V, -55 to 85 degC, 0201 (0603 Metric), RoHS, Tape and Reel")
      (fields
        (field (name "TOLERANCE") "10%")
        (field (name "CAPACITANCE") "100 nF")
        (field (name "MANUFACTURER") "Basic Passives")
      )
      (libsource (lib "Altium Content Vault") (part "CAP-NP-2"))
    )
    (comp (ref "C478")
      (value "GRM033R60J104KE19D")
      (footprint "CAPC0603X33X15LL03T05")
      (description "Chip Capacitor, 100 nF, +/- 10%, 6.3 V, -55 to 85 degC, 0201 (0603 Metric), RoHS, Tape and Reel")
      (fields
        (field (name "TOLERANCE") "10%")
        (field (name "CAPACITANCE") "100 nF")
        (field (name "MANUFACTURER") "Basic Passives")
      )
      (libsource (lib "Altium Content Vault") (part "CAP-NP-2"))
    )
    (comp (ref "C479")
      (value "GRM033R60J104KE19D")
      (footprint "CAPC0603X33X15LL03T05")
      (description "Chip Capacitor, 100 nF, +/- 10%, 6.3 V, -55 to 85 degC, 0201 (0603 Metric), RoHS, Tape and Reel")
      (fields
        (field (name "TOLERANCE") "10%")
        (field (name "CAPACITANCE") "100 nF")
        (field (name "MANUFACTURER") "Basic Passives")
      )
      (libsource (lib "Altium Content Vault") (part "CAP-NP-2"))
    )
    (comp (ref "C480")
      (value "GRM033R60J104KE19D")
      (footprint "CAPC0603X33X15LL03T05")
      (description "Chip Capacitor, 100 nF, +/- 10%, 6.3 V, -55 to 85 degC, 0201 (0603 Metric), RoHS, Tape and Reel")
      (fields
        (field (name "TOLERANCE") "10%")
        (field (name "CAPACITANCE") "100 nF")
        (field (name "MANUFACTURER") "Basic Passives")
      )
      (libsource (lib "Altium Content Vault") (part "CAP-NP-2"))
    )
    (comp (ref "L15")
      (value "742792609")
      (footprint "SMD-0603")
      (description "SMD EMI Suppression Ferrite Bead WE-CBF, Z = 30 Ohm")
      (libsource (lib "Altium Content Vault") (part "CMP-0220-00193-1"))
    )
    (comp (ref "L16")
      (value "742792609")
      (footprint "SMD-0603")
      (description "SMD EMI Suppression Ferrite Bead WE-CBF, Z = 30 Ohm")
      (libsource (lib "Altium Content Vault") (part "CMP-0220-00193-1"))
    )
    (comp (ref "R326")
      (value "ERJ-2GE0R00X")
      (footprint "RESC1005X40X25ML05T05")
      (description "Chip Resistor, 0 mOhm, +/- 5%, 100 mW, -55 to 155 degC, 0402 (1005 Metric), RoHS, Tape and Reel")
      (fields
        (field (name "TOLERANCE") "5%")
        (field (name "RESISTANCE") "0 mOhm")
        (field (name "MANUFACTURER") "Basic Passives")
      )
      (libsource (lib "Altium Content Vault") (part "RES-2"))
    )
    (comp (ref "R327")
      (value "ERJ-2GE0R00X")
      (footprint "RESC1005X40X25ML05T05")
      (description "Chip Resistor, 0 mOhm, +/- 5%, 100 mW, -55 to 155 degC, 0402 (1005 Metric), RoHS, Tape and Reel")
      (fields
        (field (name "TOLERANCE") "5%")
        (field (name "RESISTANCE") "0 mOhm")
        (field (name "MANUFACTURER") "Basic Passives")
      )
      (libsource (lib "Altium Content Vault") (part "RES-2"))
    )
  )
  (nets
    (net (code "1") (name "A10VCCAPLLHPS") (class "Default")
      (node (ref "C463") (pin "2") (pinfunction "2_2") (pintype "passive"))
      (node (ref "L16") (pin "2") (pinfunction "2_2") (pintype "passive"))
    )
    (net (code "2") (name "A10_1V0") (class "Default")
      (node (ref "C390") (pin "1") (pinfunction "1_1") (pintype "passive"))
      (node (ref "C391") (pin "2") (pinfunction "2_2") (pintype "passive"))
      (node (ref "C392") (pin "2") (pinfunction "2_2") (pintype "passive"))
      (node (ref "C393") (pin "2") (pinfunction "2_2") (pintype "passive"))
      (node (ref "C394") (pin "2") (pinfunction "2_2") (pintype "passive"))
      (node (ref "C395") (pin "2") (pinfunction "2_2") (pintype "passive"))
      (node (ref "C396") (pin "2") (pinfunction "2_2") (pintype "passive"))
      (node (ref "C397") (pin "2") (pinfunction "2_2") (pintype "passive"))
      (node (ref "C398") (pin "2") (pinfunction "2_2") (pintype "passive"))
      (node (ref "C399") (pin "2") (pinfunction "2_2") (pintype "passive"))
      (node (ref "C400") (pin "2") (pinfunction "2_2") (pintype "passive"))
      (node (ref "C401") (pin "2") (pinfunction "2_2") (pintype "passive"))
      (node (ref "C402") (pin "2") (pinfunction "2_2") (pintype "passive"))
      (node (ref "C403") (pin "2") (pinfunction "2_2") (pintype "passive"))
      (node (ref "C404") (pin "2") (pinfunction "2_2") (pintype "passive"))
      (node (ref "C405") (pin "2") (pinfunction "2_2") (pintype "passive"))
      (node (ref "C406") (pin "2") (pinfunction "2_2") (pintype "passive"))
      (node (ref "C407") (pin "2") (pinfunction "2_2") (pintype "passive"))
      (node (ref "C408") (pin "2") (pinfunction "2_2") (pintype "passive"))
      (node (ref "C409") (pin "2") (pinfunction "2_2") (pintype "passive"))
      (node (ref "C410") (pin "2") (pinfunction "2_2") (pintype "passive"))
      (node (ref "C411") (pin "2") (pinfunction "2_2") (pintype "passive"))
      (node (ref "C412") (pin "2") (pinfunction "2_2") (pintype "passive"))
      (node (ref "C413") (pin "2") (pinfunction "2_2") (pintype "passive"))
      (node (ref "C414") (pin "2") (pinfunction "2_2") (pintype "passive"))
      (node (ref "C415") (pin "2") (pinfunction "2_2") (pintype "passive"))
      (node (ref "C416") (pin "2") (pinfunction "2_2") (pintype "passive"))
      (node (ref "C417") (pin "2") (pinfunction "2_2") (pintype "passive"))
      (node (ref "C418") (pin "2") (pinfunction "2_2") (pintype "passive"))
      (node (ref "C419") (pin "2") (pinfunction "2_2") (pintype "passive"))
      (node (ref "C420") (pin "2") (pinfunction "2_2") (pintype "passive"))
      (node (ref "C421") (pin "2") (pinfunction "2_2") (pintype "passive"))
      (node (ref "C422") (pin "2") (pinfunction "2_2") (pintype "passive"))
    )
    (net (code "3") (name "A10_VCCAPLL") (class "Default")
      (node (ref "C458") (pin "2") (pinfunction "2_2") (pintype "passive"))
      (node (ref "C459") (pin "2") (pinfunction "2_2") (pintype "passive"))
      (node (ref "L15") (pin "2") (pinfunction "2_2") (pintype "passive"))
    )
    (net (code "4") (name "FMCBVADJ") (class "Default")
      (node (ref "C460") (pin "2") (pinfunction "2_2") (pintype "passive"))
      (node (ref "C461") (pin "2") (pinfunction "2_2") (pintype "passive"))
      (node (ref "C462") (pin "2") (pinfunction "2_2") (pintype "passive"))
    )
    (net (code "5") (name "GND") (class "Default")
      (node (ref "C390") (pin "2") (pinfunction "2_2") (pintype "passive"))
      (node (ref "C391") (pin "1") (pinfunction "1_1") (pintype "passive"))
      (node (ref "C392") (pin "1") (pinfunction "1_1") (pintype "passive"))
      (node (ref "C393") (pin "1") (pinfunction "1_1") (pintype "passive"))
      (node (ref "C394") (pin "1") (pinfunction "1_1") (pintype "passive"))
      (node (ref "C395") (pin "1") (pinfunction "1_1") (pintype "passive"))
      (node (ref "C396") (pin "1") (pinfunction "1_1") (pintype "passive"))
      (node (ref "C397") (pin "1") (pinfunction "1_1") (pintype "passive"))
      (node (ref "C398") (pin "1") (pinfunction "1_1") (pintype "passive"))
      (node (ref "C399") (pin "1") (pinfunction "1_1") (pintype "passive"))
      (node (ref "C400") (pin "1") (pinfunction "1_1") (pintype "passive"))
      (node (ref "C401") (pin "1") (pinfunction "1_1") (pintype "passive"))
      (node (ref "C402") (pin "1") (pinfunction "1_1") (pintype "passive"))
      (node (ref "C403") (pin "1") (pinfunction "1_1") (pintype "passive"))
      (node (ref "C404") (pin "1") (pinfunction "1_1") (pintype "passive"))
      (node (ref "C405") (pin "1") (pinfunction "1_1") (pintype "passive"))
      (node (ref "C406") (pin "1") (pinfunction "1_1") (pintype "passive"))
      (node (ref "C407") (pin "1") (pinfunction "1_1") (pintype "passive"))
      (node (ref "C408") (pin "1") (pinfunction "1_1") (pintype "passive"))
      (node (ref "C409") (pin "1") (pinfunction "1_1") (pintype "passive"))
      (node (ref "C410") (pin "1") (pinfunction "1_1") (pintype "passive"))
      (node (ref "C411") (pin "1") (pinfunction "1_1") (pintype "passive"))
      (node (ref "C412") (pin "1") (pinfunction "1_1") (pintype "passive"))
      (node (ref "C413") (pin "1") (pinfunction "1_1") (pintype "passive"))
      (node (ref "C414") (pin "1") (pinfunction "1_1") (pintype "passive"))
      (node (ref "C415") (pin "1") (pinfunction "1_1") (pintype "passive"))
      (node (ref "C416") (pin "1") (pinfunction "1_1") (pintype "passive"))
      (node (ref "C417") (pin "1") (pinfunction "1_1") (pintype "passive"))
      (node (ref "C418") (pin "1") (pinfunction "1_1") (pintype "passive"))
      (node (ref "C419") (pin "1") (pinfunction "1_1") (pintype "passive"))
      (node (ref "C420") (pin "1") (pinfunction "1_1") (pintype "passive"))
      (node (ref "C421") (pin "1") (pinfunction "1_1") (pintype "passive"))
      (node (ref "C422") (pin "1") (pinfunction "1_1") (pintype "passive"))
      (node (ref "C423") (pin "1") (pinfunction "1_1") (pintype "passive"))
      (node (ref "C424") (pin "1") (pinfunction "1_1") (pintype "passive"))
      (node (ref "C425") (pin "1") (pinfunction "1_1") (pintype "passive"))
      (node (ref "C426") (pin "1") (pinfunction "1_1") (pintype "passive"))
      (node (ref "C427") (pin "1") (pinfunction "1_1") (pintype "passive"))
      (node (ref "C428") (pin "1") (pinfunction "1_1") (pintype "passive"))
      (node (ref "C429") (pin "1") (pinfunction "1_1") (pintype "passive"))
      (node (ref "C430") (pin "1") (pinfunction "1_1") (pintype "passive"))
      (node (ref "C431") (pin "1") (pinfunction "1_1") (pintype "passive"))
      (node (ref "C432") (pin "1") (pinfunction "1_1") (pintype "passive"))
      (node (ref "C433") (pin "1") (pinfunction "1_1") (pintype "passive"))
      (node (ref "C434") (pin "1") (pinfunction "1_1") (pintype "passive"))
      (node (ref "C435") (pin "1") (pinfunction "1_1") (pintype "passive"))
      (node (ref "C436") (pin "1") (pinfunction "1_1") (pintype "passive"))
      (node (ref "C437") (pin "1") (pinfunction "1_1") (pintype "passive"))
      (node (ref "C438") (pin "1") (pinfunction "1_1") (pintype "passive"))
      (node (ref "C439") (pin "1") (pinfunction "1_1") (pintype "passive"))
      (node (ref "C440") (pin "1") (pinfunction "1_1") (pintype "passive"))
      (node (ref "C441") (pin "1") (pinfunction "1_1") (pintype "passive"))
      (node (ref "C442") (pin "1") (pinfunction "1_1") (pintype "passive"))
      (node (ref "C443") (pin "1") (pinfunction "1_1") (pintype "passive"))
      (node (ref "C444") (pin "1") (pinfunction "1_1") (pintype "passive"))
      (node (ref "C445") (pin "1") (pinfunction "1_1") (pintype "passive"))
      (node (ref "C446") (pin "1") (pinfunction "1_1") (pintype "passive"))
      (node (ref "C447") (pin "1") (pinfunction "1_1") (pintype "passive"))
      (node (ref "C448") (pin "1") (pinfunction "1_1") (pintype "passive"))
      (node (ref "C449") (pin "1") (pinfunction "1_1") (pintype "passive"))
      (node (ref "C450") (pin "1") (pinfunction "1_1") (pintype "passive"))
      (node (ref "C451") (pin "1") (pinfunction "1_1") (pintype "passive"))
      (node (ref "C452") (pin "1") (pinfunction "1_1") (pintype "passive"))
      (node (ref "C453") (pin "1") (pinfunction "1_1") (pintype "passive"))
      (node (ref "C454") (pin "1") (pinfunction "1_1") (pintype "passive"))
      (node (ref "C455") (pin "1") (pinfunction "1_1") (pintype "passive"))
      (node (ref "C456") (pin "1") (pinfunction "1_1") (pintype "passive"))
      (node (ref "C457") (pin "1") (pinfunction "1_1") (pintype "passive"))
      (node (ref "C458") (pin "1") (pinfunction "1_1") (pintype "passive"))
      (node (ref "C459") (pin "1") (pinfunction "1_1") (pintype "passive"))
      (node (ref "C460") (pin "1") (pinfunction "1_1") (pintype "passive"))
      (node (ref "C461") (pin "1") (pinfunction "1_1") (pintype "passive"))
      (node (ref "C462") (pin "1") (pinfunction "1_1") (pintype "passive"))
      (node (ref "C463") (pin "1") (pinfunction "1_1") (pintype "passive"))
      (node (ref "C464") (pin "1") (pinfunction "1_1") (pintype "passive"))
      (node (ref "C465") (pin "1") (pinfunction "1_1") (pintype "passive"))
      (node (ref "C466") (pin "1") (pinfunction "1_1") (pintype "passive"))
      (node (ref "C467") (pin "1") (pinfunction "1_1") (pintype "passive"))
      (node (ref "C468") (pin "1") (pinfunction "1_1") (pintype "passive"))
      (node (ref "C469") (pin "1") (pinfunction "1_1") (pintype "passive"))
      (node (ref "C470") (pin "1") (pinfunction "1_1") (pintype "passive"))
      (node (ref "C471") (pin "1") (pinfunction "1_1") (pintype "passive"))
      (node (ref "C472") (pin "1") (pinfunction "1_1") (pintype "passive"))
      (node (ref "C473") (pin "1") (pinfunction "1_1") (pintype "passive"))
      (node (ref "C474") (pin "1") (pinfunction "1_1") (pintype "passive"))
      (node (ref "C475") (pin "1") (pinfunction "1_1") (pintype "passive"))
      (node (ref "C476") (pin "1") (pinfunction "1_1") (pintype "passive"))
      (node (ref "C477") (pin "1") (pinfunction "1_1") (pintype "passive"))
      (node (ref "C478") (pin "1") (pinfunction "1_1") (pintype "passive"))
      (node (ref "C479") (pin "1") (pinfunction "1_1") (pintype "passive"))
      (node (ref "C480") (pin "1") (pinfunction "1_1") (pintype "passive"))
    )
    (net (code "6") (name "IO_1V8") (class "Default")
      (node (ref "C445") (pin "2") (pinfunction "2_2") (pintype "passive"))
      (node (ref "C446") (pin "2") (pinfunction "2_2") (pintype "passive"))
      (node (ref "C447") (pin "2") (pinfunction "2_2") (pintype "passive"))
      (node (ref "C448") (pin "2") (pinfunction "2_2") (pintype "passive"))
      (node (ref "C449") (pin "2") (pinfunction "2_2") (pintype "passive"))
      (node (ref "C450") (pin "2") (pinfunction "2_2") (pintype "passive"))
      (node (ref "C451") (pin "2") (pinfunction "2_2") (pintype "passive"))
      (node (ref "C452") (pin "2") (pinfunction "2_2") (pintype "passive"))
      (node (ref "C453") (pin "2") (pinfunction "2_2") (pintype "passive"))
      (node (ref "C454") (pin "2") (pinfunction "2_2") (pintype "passive"))
      (node (ref "C455") (pin "2") (pinfunction "2_2") (pintype "passive"))
      (node (ref "C456") (pin "2") (pinfunction "2_2") (pintype "passive"))
      (node (ref "C457") (pin "2") (pinfunction "2_2") (pintype "passive"))
      (node (ref "R326") (pin "1") (pinfunction "1_1") (pintype "passive"))
    )
    (net (code "7") (name "PLL_1V8") (class "Default")
      (node (ref "C423") (pin "2") (pinfunction "2_2") (pintype "passive"))
      (node (ref "C424") (pin "2") (pinfunction "2_2") (pintype "passive"))
      (node (ref "C425") (pin "2") (pinfunction "2_2") (pintype "passive"))
      (node (ref "C426") (pin "2") (pinfunction "2_2") (pintype "passive"))
      (node (ref "C427") (pin "2") (pinfunction "2_2") (pintype "passive"))
      (node (ref "C428") (pin "2") (pinfunction "2_2") (pintype "passive"))
      (node (ref "C429") (pin "2") (pinfunction "2_2") (pintype "passive"))
      (node (ref "C430") (pin "2") (pinfunction "2_2") (pintype "passive"))
      (node (ref "C431") (pin "2") (pinfunction "2_2") (pintype "passive"))
      (node (ref "C432") (pin "2") (pinfunction "2_2") (pintype "passive"))
      (node (ref "C433") (pin "2") (pinfunction "2_2") (pintype "passive"))
      (node (ref "C434") (pin "2") (pinfunction "2_2") (pintype "passive"))
      (node (ref "C435") (pin "2") (pinfunction "2_2") (pintype "passive"))
      (node (ref "C436") (pin "2") (pinfunction "2_2") (pintype "passive"))
      (node (ref "C437") (pin "2") (pinfunction "2_2") (pintype "passive"))
      (node (ref "C438") (pin "2") (pinfunction "2_2") (pintype "passive"))
      (node (ref "C439") (pin "2") (pinfunction "2_2") (pintype "passive"))
      (node (ref "C440") (pin "2") (pinfunction "2_2") (pintype "passive"))
      (node (ref "C441") (pin "2") (pinfunction "2_2") (pintype "passive"))
      (node (ref "C442") (pin "2") (pinfunction "2_2") (pintype "passive"))
      (node (ref "C443") (pin "2") (pinfunction "2_2") (pintype "passive"))
      (node (ref "C444") (pin "2") (pinfunction "2_2") (pintype "passive"))
      (node (ref "L15") (pin "1") (pinfunction "1_1") (pintype "passive"))
      (node (ref "L16") (pin "1") (pinfunction "1_1") (pintype "passive"))
      (node (ref "R327") (pin "1") (pinfunction "1_1") (pintype "passive"))
    )
    (net (code "8") (name "VCCIOREF_HPS") (class "Default")
      (node (ref "C480") (pin "2") (pinfunction "2_2") (pintype "passive"))
      (node (ref "R327") (pin "2") (pinfunction "2_2") (pintype "passive"))
    )
    (net (code "9") (name "VCCIO_HPS") (class "Default")
      (node (ref "C464") (pin "2") (pinfunction "2_2") (pintype "passive"))
      (node (ref "R326") (pin "2") (pinfunction "2_2") (pintype "passive"))
    )
    (net (code "10") (name "VDD_DDR") (class "Default")
      (node (ref "C465") (pin "2") (pinfunction "2_2") (pintype "passive"))
      (node (ref "C466") (pin "2") (pinfunction "2_2") (pintype "passive"))
      (node (ref "C467") (pin "2") (pinfunction "2_2") (pintype "passive"))
      (node (ref "C468") (pin "2") (pinfunction "2_2") (pintype "passive"))
      (node (ref "C469") (pin "2") (pinfunction "2_2") (pintype "passive"))
      (node (ref "C470") (pin "2") (pinfunction "2_2") (pintype "passive"))
      (node (ref "C471") (pin "2") (pinfunction "2_2") (pintype "passive"))
      (node (ref "C472") (pin "2") (pinfunction "2_2") (pintype "passive"))
      (node (ref "C473") (pin "2") (pinfunction "2_2") (pintype "passive"))
      (node (ref "C474") (pin "2") (pinfunction "2_2") (pintype "passive"))
      (node (ref "C475") (pin "2") (pinfunction "2_2") (pintype "passive"))
      (node (ref "C476") (pin "2") (pinfunction "2_2") (pintype "passive"))
      (node (ref "C477") (pin "2") (pinfunction "2_2") (pintype "passive"))
      (node (ref "C478") (pin "2") (pinfunction "2_2") (pintype "passive"))
      (node (ref "C479") (pin "2") (pinfunction "2_2") (pintype "passive"))
    )
  )
)
